# gtp.net
KiCad netlist of a schematic drawn in Altium Designer
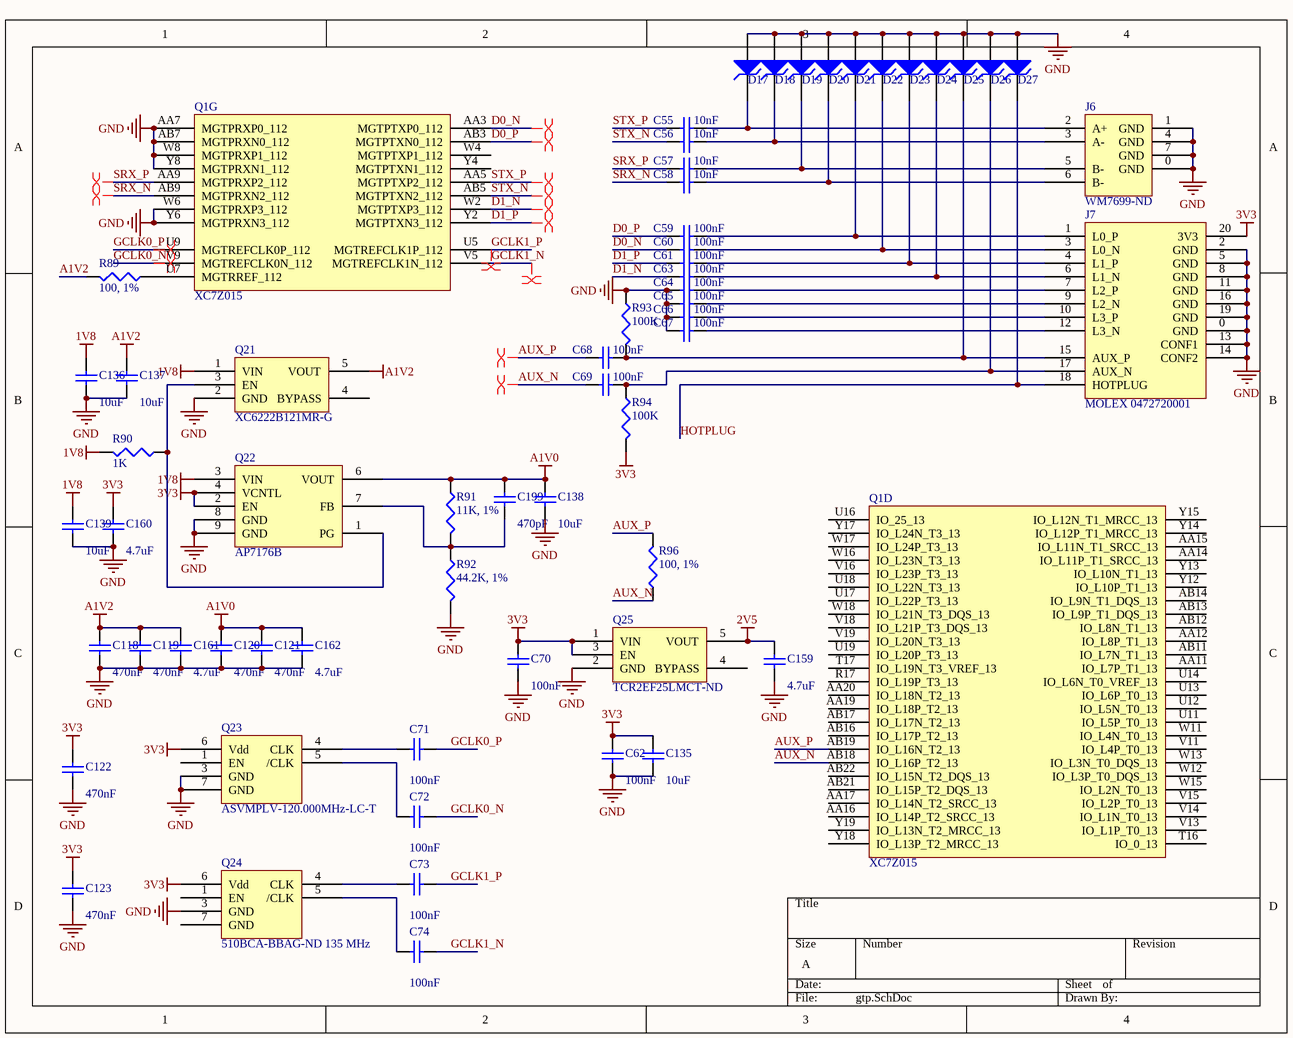
[diagram p0: gtp.SchDoc]

(export (version "E")
  (design (tool "Eeschema 10.0.6"))
  (components
    (comp (ref "C55")
      (value "10nF")
      (footprint "CAPC1005X06L")
      (description "Capacitor")
      (fields (field (name "Comment") "Cap") (field (name "PUBLISHER") "Altium Limited"))
      (libsource (lib "Miscellaneous Devices") (part "Cap"))
    )
    (comp (ref "C56")
      (value "10nF")
      (footprint "CAPC1005X06L")
      (description "Capacitor")
      (fields (field (name "Comment") "Cap") (field (name "PUBLISHER") "Altium Limited"))
      (libsource (lib "Miscellaneous Devices") (part "Cap"))
    )
    (comp (ref "C57")
      (value "10nF")
      (footprint "CAPC1005X06L")
      (description "Capacitor")
      (fields (field (name "Comment") "Cap") (field (name "PUBLISHER") "Altium Limited"))
      (libsource (lib "Miscellaneous Devices") (part "Cap"))
    )
    (comp (ref "C58")
      (value "10nF")
      (footprint "CAPC1005X06L")
      (description "Capacitor")
      (fields (field (name "Comment") "Cap") (field (name "PUBLISHER") "Altium Limited"))
      (libsource (lib "Miscellaneous Devices") (part "Cap"))
    )
    (comp (ref "C59")
      (value "100nF")
      (footprint "CAPC1005X06L")
      (description "Capacitor")
      (fields (field (name "Comment") "Cap") (field (name "PUBLISHER") "Altium Limited"))
      (libsource (lib "Miscellaneous Devices") (part "Cap"))
    )
    (comp (ref "C60")
      (value "100nF")
      (footprint "CAPC1005X06L")
      (description "Capacitor")
      (fields (field (name "Comment") "Cap") (field (name "PUBLISHER") "Altium Limited"))
      (libsource (lib "Miscellaneous Devices") (part "Cap"))
    )
    (comp (ref "C61")
      (value "100nF")
      (footprint "CAPC1005X06L")
      (description "Capacitor")
      (fields (field (name "Comment") "Cap") (field (name "PUBLISHER") "Altium Limited"))
      (libsource (lib "Miscellaneous Devices") (part "Cap"))
    )
    (comp (ref "C62")
      (value "100nF")
      (footprint "CAPC1005X06L")
      (description "Capacitor")
      (fields (field (name "Comment") "Cap") (field (name "PUBLISHER") "Altium Limited"))
      (libsource (lib "Miscellaneous Devices") (part "Cap"))
    )
    (comp (ref "C63")
      (value "100nF")
      (footprint "CAPC1005X06L")
      (description "Capacitor")
      (fields (field (name "Comment") "Cap") (field (name "PUBLISHER") "Altium Limited"))
      (libsource (lib "Miscellaneous Devices") (part "Cap"))
    )
    (comp (ref "C64")
      (value "100nF")
      (footprint "CAPC1005X06L")
      (description "Capacitor")
      (fields (field (name "Comment") "Cap") (field (name "PUBLISHER") "Altium Limited"))
      (libsource (lib "Miscellaneous Devices") (part "Cap"))
    )
    (comp (ref "C65")
      (value "100nF")
      (footprint "CAPC1005X06L")
      (description "Capacitor")
      (fields (field (name "Comment") "Cap") (field (name "PUBLISHER") "Altium Limited"))
      (libsource (lib "Miscellaneous Devices") (part "Cap"))
    )
    (comp (ref "C66")
      (value "100nF")
      (footprint "CAPC1005X06L")
      (description "Capacitor")
      (fields (field (name "Comment") "Cap") (field (name "PUBLISHER") "Altium Limited"))
      (libsource (lib "Miscellaneous Devices") (part "Cap"))
    )
    (comp (ref "C67")
      (value "100nF")
      (footprint "CAPC1005X06L")
      (description "Capacitor")
      (fields (field (name "Comment") "Cap") (field (name "PUBLISHER") "Altium Limited"))
      (libsource (lib "Miscellaneous Devices") (part "Cap"))
    )
    (comp (ref "C68")
      (value "100nF")
      (footprint "CAPC1005X06L")
      (description "Capacitor")
      (fields (field (name "Comment") "Cap") (field (name "PUBLISHER") "Altium Limited"))
      (libsource (lib "Miscellaneous Devices") (part "Cap"))
    )
    (comp (ref "C69")
      (value "100nF")
      (footprint "CAPC1005X06L")
      (description "Capacitor")
      (fields (field (name "Comment") "Cap") (field (name "PUBLISHER") "Altium Limited"))
      (libsource (lib "Miscellaneous Devices") (part "Cap"))
    )
    (comp (ref "C70")
      (value "100nF")
      (footprint "CAPC1005X06L")
      (description "Capacitor")
      (fields (field (name "Comment") "Cap") (field (name "PUBLISHER") "Altium Limited"))
      (libsource (lib "Miscellaneous Devices") (part "Cap"))
    )
    (comp (ref "C71")
      (value "100nF")
      (footprint "CAPC1005X06L")
      (description "Capacitor")
      (fields (field (name "Comment") "Cap") (field (name "PUBLISHER") "Altium Limited"))
      (libsource (lib "Miscellaneous Devices") (part "Cap"))
    )
    (comp (ref "C72")
      (value "100nF")
      (footprint "CAPC1005X06L")
      (description "Capacitor")
      (fields (field (name "Comment") "Cap") (field (name "PUBLISHER") "Altium Limited"))
      (libsource (lib "Miscellaneous Devices") (part "Cap"))
    )
    (comp (ref "C73")
      (value "100nF")
      (footprint "CAPC1005X06L")
      (description "Capacitor")
      (fields (field (name "Comment") "Cap") (field (name "PUBLISHER") "Altium Limited"))
      (libsource (lib "Miscellaneous Devices") (part "Cap"))
    )
    (comp (ref "C74")
      (value "100nF")
      (footprint "CAPC1005X06L")
      (description "Capacitor")
      (fields (field (name "Comment") "Cap") (field (name "PUBLISHER") "Altium Limited"))
      (libsource (lib "Miscellaneous Devices") (part "Cap"))
    )
    (comp (ref "C118")
      (value "470nF")
      (footprint "CAPC1005X06L")
      (description "Capacitor")
      (fields (field (name "Comment") "JMK105BJ474KV-F") (field (name "PUBLISHER") "Altium Limited"))
      (libsource (lib "Miscellaneous Devices") (part "Cap"))
    )
    (comp (ref "C119")
      (value "470nF")
      (footprint "CAPC1005X06L")
      (description "Capacitor")
      (fields (field (name "Comment") "JMK105BJ474KV-F") (field (name "PUBLISHER") "Altium Limited"))
      (libsource (lib "Miscellaneous Devices") (part "Cap"))
    )
    (comp (ref "C120")
      (value "470nF")
      (footprint "CAPC1005X06L")
      (description "Capacitor")
      (fields (field (name "Comment") "JMK105BJ474KV-F") (field (name "PUBLISHER") "Altium Limited"))
      (libsource (lib "Miscellaneous Devices") (part "Cap"))
    )
    (comp (ref "C121")
      (value "470nF")
      (footprint "CAPC1005X06L")
      (description "Capacitor")
      (fields (field (name "Comment") "JMK105BJ474KV-F") (field (name "PUBLISHER") "Altium Limited"))
      (libsource (lib "Miscellaneous Devices") (part "Cap"))
    )
    (comp (ref "C122")
      (value "470nF")
      (footprint "CAPC1005X06L")
      (description "Capacitor")
      (fields (field (name "Comment") "JMK105BJ474KV-F") (field (name "PUBLISHER") "Altium Limited"))
      (libsource (lib "Miscellaneous Devices") (part "Cap"))
    )
    (comp (ref "C123")
      (value "470nF")
      (footprint "CAPC1005X06L")
      (description "Capacitor")
      (fields (field (name "Comment") "JMK105BJ474KV-F") (field (name "PUBLISHER") "Altium Limited"))
      (libsource (lib "Miscellaneous Devices") (part "Cap"))
    )
    (comp (ref "C135")
      (value "10uF")
      (footprint "CAPC1608X90N")
      (description "Capacitor")
      (fields (field (name "Comment") "GRM188R60G106ME47") (field (name "PUBLISHER") "Altium Limited"))
      (libsource (lib "Miscellaneous Devices") (part "Cap"))
    )
    (comp (ref "C136")
      (value "10uF")
      (footprint "CAPC1608X90N")
      (description "Capacitor")
      (fields (field (name "Comment") "GRM188R60G106ME47") (field (name "PUBLISHER") "Altium Limited"))
      (libsource (lib "Miscellaneous Devices") (part "Cap"))
    )
    (comp (ref "C137")
      (value "10uF")
      (footprint "CAPC1608X90N")
      (description "Capacitor")
      (fields (field (name "Comment") "GRM188R60G106ME47") (field (name "PUBLISHER") "Altium Limited"))
      (libsource (lib "Miscellaneous Devices") (part "Cap"))
    )
    (comp (ref "C138")
      (value "10uF")
      (footprint "CAPC1608X90N")
      (description "Capacitor")
      (fields (field (name "Comment") "GRM188R60G106ME47") (field (name "PUBLISHER") "Altium Limited"))
      (libsource (lib "Miscellaneous Devices") (part "Cap"))
    )
    (comp (ref "C139")
      (value "10uF")
      (footprint "CAPC1608X90N")
      (description "Capacitor")
      (fields (field (name "Comment") "GRM188R60G106ME47") (field (name "PUBLISHER") "Altium Limited"))
      (libsource (lib "Miscellaneous Devices") (part "Cap"))
    )
    (comp (ref "C159")
      (value "4.7uF")
      (footprint "CAPC1608X90N")
      (description "Capacitor")
      (fields (field (name "Comment") "GRM188R60J475ME19D") (field (name "PUBLISHER") "Altium Limited"))
      (libsource (lib "Miscellaneous Devices") (part "Cap"))
    )
    (comp (ref "C160")
      (value "4.7uF")
      (footprint "CAPC1608X90N")
      (description "Capacitor")
      (fields (field (name "Comment") "GRM188R60J475ME19D") (field (name "PUBLISHER") "Altium Limited"))
      (libsource (lib "Miscellaneous Devices") (part "Cap"))
    )
    (comp (ref "C161")
      (value "4.7uF")
      (footprint "CAPC1608X90N")
      (description "Capacitor")
      (fields (field (name "Comment") "GRM188R60J475ME19D") (field (name "PUBLISHER") "Altium Limited"))
      (libsource (lib "Miscellaneous Devices") (part "Cap"))
    )
    (comp (ref "C162")
      (value "4.7uF")
      (footprint "CAPC1608X90N")
      (description "Capacitor")
      (fields (field (name "Comment") "GRM188R60J475ME19D") (field (name "PUBLISHER") "Altium Limited"))
      (libsource (lib "Miscellaneous Devices") (part "Cap"))
    )
    (comp (ref "C199")
      (value "470pF")
      (footprint "CAPC1608X90N")
      (description "Capacitor")
      (fields (field (name "Comment") "CL10C471JB8NCNC") (field (name "PUBLISHER") "Altium Limited"))
      (libsource (lib "Miscellaneous Devices") (part "Cap"))
    )
    (comp (ref "D17")
      (value "EZAEG2A")
      (footprint "CAPC1005X55N")
      (description "Zener Diode")
      (fields (field (name "PUBLISHER") "Altium Limited"))
      (libsource (lib "Miscellaneous Devices") (part "D Zener"))
    )
    (comp (ref "D18")
      (value "EZAEG2A")
      (footprint "CAPC1005X55N")
      (description "Zener Diode")
      (fields (field (name "PUBLISHER") "Altium Limited"))
      (libsource (lib "Miscellaneous Devices") (part "D Zener"))
    )
    (comp (ref "D19")
      (value "EZAEG2A")
      (footprint "CAPC1005X55N")
      (description "Zener Diode")
      (fields (field (name "PUBLISHER") "Altium Limited"))
      (libsource (lib "Miscellaneous Devices") (part "D Zener"))
    )
    (comp (ref "D20")
      (value "EZAEG2A")
      (footprint "CAPC1005X55N")
      (description "Zener Diode")
      (fields (field (name "PUBLISHER") "Altium Limited"))
      (libsource (lib "Miscellaneous Devices") (part "D Zener"))
    )
    (comp (ref "D21")
      (value "EZAEG2A")
      (footprint "CAPC1005X55N")
      (description "Zener Diode")
      (fields (field (name "PUBLISHER") "Altium Limited"))
      (libsource (lib "Miscellaneous Devices") (part "D Zener"))
    )
    (comp (ref "D22")
      (value "EZAEG2A")
      (footprint "CAPC1005X55N")
      (description "Zener Diode")
      (fields (field (name "PUBLISHER") "Altium Limited"))
      (libsource (lib "Miscellaneous Devices") (part "D Zener"))
    )
    (comp (ref "D23")
      (value "EZAEG2A")
      (footprint "CAPC1005X55N")
      (description "Zener Diode")
      (fields (field (name "PUBLISHER") "Altium Limited"))
      (libsource (lib "Miscellaneous Devices") (part "D Zener"))
    )
    (comp (ref "D24")
      (value "EZAEG2A")
      (footprint "CAPC1005X55N")
      (description "Zener Diode")
      (fields (field (name "PUBLISHER") "Altium Limited"))
      (libsource (lib "Miscellaneous Devices") (part "D Zener"))
    )
    (comp (ref "D25")
      (value "EZAEG2A")
      (footprint "CAPC1005X55N")
      (description "Zener Diode")
      (fields (field (name "PUBLISHER") "Altium Limited"))
      (libsource (lib "Miscellaneous Devices") (part "D Zener"))
    )
    (comp (ref "D26")
      (value "EZAEG2A")
      (footprint "CAPC1005X55N")
      (description "Zener Diode")
      (fields (field (name "PUBLISHER") "Altium Limited"))
      (libsource (lib "Miscellaneous Devices") (part "D Zener"))
    )
    (comp (ref "D27")
      (value "EZAEG2A")
      (footprint "CAPC1005X55N")
      (description "Zener Diode")
      (fields (field (name "PUBLISHER") "Altium Limited"))
      (libsource (lib "Miscellaneous Devices") (part "D Zener"))
    )
    (comp (ref "J6")
      (value "WM7699-ND")
      (footprint "WM7699-ND")
      (libsource (lib "schlib") (part "WM7699-ND"))
    )
    (comp (ref "J7")
      (value "MOLEX 0472720001")
      (footprint "MOLEX0472720001")
      (libsource (lib "schlib") (part "DP"))
    )
    (comp (ref "Q1") (value "XC7Z015") (footprint "BGA484x22") (libsource (lib "schlib") (part "XC7Z015")))
    (comp (ref "Q21") (value "XC6222B121MR-G") (footprint "SOT23-5") (libsource (lib "schlib") (part "LDO")))
    (comp (ref "Q22")
      (value "AP7176B")
      (footprint "SOIC127P600X135_HS-9N")
      (libsource (lib "schlib") (part "AP7176B"))
    )
    (comp (ref "Q23")
      (value "ASVMPLV-120.000MHz-LC-T")
      (footprint "ASVMP")
      (libsource (lib "schlib") (part "ASVMP"))
    )
    (comp (ref "Q24")
      (value "510BCA-BBAG-ND 135 MHz")
      (footprint "Si510")
      (libsource (lib "schlib") (part "ASVMP"))
    )
    (comp (ref "Q25") (value "TCR2EF25LMCT-ND") (footprint "SOT23-5") (libsource (lib "schlib") (part "LDO")))
    (comp (ref "R89")
      (value "100, 1%")
      (footprint "J1-0603")
      (description "Resistor")
      (fields (field (name "Comment") "RC1608F101CS") (field (name "PUBLISHER") "Altium Limited"))
      (libsource (lib "Miscellaneous Devices") (part "Res3"))
    )
    (comp (ref "R90")
      (value "1K")
      (footprint "J1-0603")
      (description "Resistor")
      (fields (field (name "Comment") "RC1608J102CS") (field (name "PUBLISHER") "Altium Limited"))
      (libsource (lib "Miscellaneous Devices") (part "Res3"))
    )
    (comp (ref "R91")
      (value "11K, 1%")
      (footprint "J1-0603")
      (description "Resistor")
      (fields (field (name "Comment") "RC1608F113CS") (field (name "PUBLISHER") "Altium Limited"))
      (libsource (lib "Miscellaneous Devices") (part "Res3"))
    )
    (comp (ref "R92")
      (value "44.2K, 1%")
      (footprint "J1-0603")
      (description "Resistor")
      (fields (field (name "Comment") "RC1608F4422CS") (field (name "PUBLISHER") "Altium Limited"))
      (libsource (lib "Miscellaneous Devices") (part "Res3"))
    )
    (comp (ref "R93")
      (value "100K")
      (footprint "J1-0603")
      (description "Resistor")
      (fields (field (name "Comment") "RC1608F104CS") (field (name "PUBLISHER") "Altium Limited"))
      (libsource (lib "Miscellaneous Devices") (part "Res3"))
    )
    (comp (ref "R94")
      (value "100K")
      (footprint "J1-0603")
      (description "Resistor")
      (fields (field (name "Comment") "RC1608F104CS") (field (name "PUBLISHER") "Altium Limited"))
      (libsource (lib "Miscellaneous Devices") (part "Res3"))
    )
    (comp (ref "R96")
      (value "100, 1%")
      (footprint "J1-0603")
      (description "Resistor")
      (fields (field (name "Comment") "RC1608F101CS") (field (name "PUBLISHER") "Altium Limited"))
      (libsource (lib "Miscellaneous Devices") (part "Res3"))
    )
  )
  (nets
    (net (code "1") (name "/AUX_N") (class "Default")
      (node (ref "C69") (pin "2") (pinfunction "2_2") (pintype "passive"))
      (node (ref "Q1") (pin "AB18") (pinfunction "IO_L16P_T2_13_AB18") (pintype "passive"))
      (node (ref "R96") (pin "1") (pinfunction "1_1") (pintype "passive"))
    )
    (net (code "2") (name "/AUX_P") (class "Default")
      (node (ref "C68") (pin "2") (pinfunction "2_2") (pintype "passive"))
      (node (ref "Q1") (pin "AB19") (pinfunction "IO_L16N_T2_13_AB19") (pintype "passive"))
      (node (ref "R96") (pin "2") (pinfunction "2_2") (pintype "passive"))
    )
    (net (code "3") (name "/D0_N") (class "Default")
      (node (ref "C60") (pin "2") (pinfunction "2_2") (pintype "passive"))
      (node (ref "Q1") (pin "AA3") (pinfunction "MGTPTXP0_112_AA3") (pintype "passive"))
    )
    (net (code "4") (name "/D0_P") (class "Default")
      (node (ref "C59") (pin "2") (pinfunction "2_2") (pintype "passive"))
      (node (ref "Q1") (pin "AB3") (pinfunction "MGTPTXN0_112_AB3") (pintype "passive"))
    )
    (net (code "5") (name "/D1_N") (class "Default")
      (node (ref "C63") (pin "2") (pinfunction "2_2") (pintype "passive"))
      (node (ref "Q1") (pin "W2") (pinfunction "MGTPTXP3_112_W2") (pintype "passive"))
    )
    (net (code "6") (name "/D1_P") (class "Default")
      (node (ref "C61") (pin "2") (pinfunction "2_2") (pintype "passive"))
      (node (ref "Q1") (pin "Y2") (pinfunction "MGTPTXN3_112_Y2") (pintype "passive"))
    )
    (net (code "7") (name "/GCLK0_N") (class "Default")
      (node (ref "C72") (pin "1") (pinfunction "1_1") (pintype "passive"))
      (node (ref "Q1") (pin "V9") (pinfunction "MGTREFCLK0N_112_V9") (pintype "passive"))
    )
    (net (code "8") (name "/GCLK0_P") (class "Default")
      (node (ref "C71") (pin "1") (pinfunction "1_1") (pintype "passive"))
      (node (ref "Q1") (pin "U9") (pinfunction "MGTREFCLK0P_112_U9") (pintype "passive"))
    )
    (net (code "9") (name "/GCLK1_N") (class "Default")
      (node (ref "C74") (pin "1") (pinfunction "1_1") (pintype "passive"))
      (node (ref "Q1") (pin "V5") (pinfunction "MGTREFCLK1N_112_V5") (pintype "passive"))
    )
    (net (code "10") (name "/GCLK1_P") (class "Default")
      (node (ref "C73") (pin "1") (pinfunction "1_1") (pintype "passive"))
      (node (ref "Q1") (pin "U5") (pinfunction "MGTREFCLK1P_112_U5") (pintype "passive"))
    )
    (net (code "11") (name "/HOTPLUG") (class "Default")
      (node (ref "D27") (pin "2") (pinfunction "K_2") (pintype "passive"))
      (node (ref "J7") (pin "18") (pinfunction "HOTPLUG_18") (pintype "passive"))
    )
    (net (code "12") (name "/SRX_N") (class "Default")
      (node (ref "C58") (pin "2") (pinfunction "2_2") (pintype "passive"))
      (node (ref "Q1") (pin "AB9") (pinfunction "MGTPRXN2_112_AB9") (pintype "passive"))
    )
    (net (code "13") (name "/SRX_P") (class "Default")
      (node (ref "C57") (pin "2") (pinfunction "2_2") (pintype "passive"))
      (node (ref "Q1") (pin "AA9") (pinfunction "MGTPRXP2_112_AA9") (pintype "passive"))
    )
    (net (code "14") (name "/STX_N") (class "Default")
      (node (ref "C56") (pin "2") (pinfunction "2_2") (pintype "passive"))
      (node (ref "Q1") (pin "AB5") (pinfunction "MGTPTXN2_112_AB5") (pintype "passive"))
    )
    (net (code "15") (name "/STX_P") (class "Default")
      (node (ref "C55") (pin "2") (pinfunction "2_2") (pintype "passive"))
      (node (ref "Q1") (pin "AA5") (pinfunction "MGTPTXP2_112_AA5") (pintype "passive"))
    )
    (net (code "16") (name "1V8") (class "Default")
      (node (ref "C136") (pin "2") (pinfunction "2_2") (pintype "passive"))
      (node (ref "C139") (pin "2") (pinfunction "2_2") (pintype "passive"))
      (node (ref "Q21") (pin "1") (pinfunction "VIN_1") (pintype "passive"))
      (node (ref "Q22") (pin "3") (pinfunction "VIN_3") (pintype "passive"))
      (node (ref "R90") (pin "2") (pinfunction "2_2") (pintype "passive"))
    )
    (net (code "17") (name "2V5") (class "Default")
      (node (ref "C159") (pin "1") (pinfunction "1_1") (pintype "passive"))
      (node (ref "Q25") (pin "5") (pinfunction "VOUT_5") (pintype "passive"))
    )
    (net (code "18") (name "3V3") (class "Default")
      (node (ref "C122") (pin "2") (pinfunction "2_2") (pintype "passive"))
      (node (ref "C123") (pin "2") (pinfunction "2_2") (pintype "passive"))
      (node (ref "C135") (pin "2") (pinfunction "2_2") (pintype "passive"))
      (node (ref "C160") (pin "1") (pinfunction "1_1") (pintype "passive"))
      (node (ref "C62") (pin "2") (pinfunction "2_2") (pintype "passive"))
      (node (ref "C70") (pin "2") (pinfunction "2_2") (pintype "passive"))
      (node (ref "J7") (pin "20") (pinfunction "3V3_20") (pintype "passive"))
      (node (ref "Q22") (pin "2") (pinfunction "EN_2") (pintype "passive"))
      (node (ref "Q22") (pin "4") (pinfunction "VCNTL_4") (pintype "passive"))
      (node (ref "Q23") (pin "6") (pinfunction "Vdd_6") (pintype "passive"))
      (node (ref "Q24") (pin "6") (pinfunction "Vdd_6") (pintype "passive"))
      (node (ref "Q25") (pin "1") (pinfunction "VIN_1") (pintype "passive"))
      (node (ref "Q25") (pin "3") (pinfunction "EN_3") (pintype "passive"))
      (node (ref "R94") (pin "2") (pinfunction "2_2") (pintype "passive"))
    )
    (net (code "19") (name "A1V0") (class "Default")
      (node (ref "C120") (pin "2") (pinfunction "2_2") (pintype "passive"))
      (node (ref "C121") (pin "2") (pinfunction "2_2") (pintype "passive"))
      (node (ref "C138") (pin "2") (pinfunction "2_2") (pintype "passive"))
      (node (ref "C162") (pin "1") (pinfunction "1_1") (pintype "passive"))
      (node (ref "C199") (pin "1") (pinfunction "1_1") (pintype "passive"))
      (node (ref "Q22") (pin "6") (pinfunction "VOUT_6") (pintype "passive"))
      (node (ref "R91") (pin "1") (pinfunction "1_1") (pintype "passive"))
    )
    (net (code "20") (name "A1V2") (class "Default")
      (node (ref "C118") (pin "2") (pinfunction "2_2") (pintype "passive"))
      (node (ref "C119") (pin "2") (pinfunction "2_2") (pintype "passive"))
      (node (ref "C137") (pin "2") (pinfunction "2_2") (pintype "passive"))
      (node (ref "C161") (pin "1") (pinfunction "1_1") (pintype "passive"))
      (node (ref "Q21") (pin "5") (pinfunction "VOUT_5") (pintype "passive"))
      (node (ref "R89") (pin "2") (pinfunction "2_2") (pintype "passive"))
    )
    (net (code "21") (name "GND") (class "Default")
      (node (ref "C118") (pin "1") (pinfunction "1_1") (pintype "passive"))
      (node (ref "C119") (pin "1") (pinfunction "1_1") (pintype "passive"))
      (node (ref "C120") (pin "1") (pinfunction "1_1") (pintype "passive"))
      (node (ref "C121") (pin "1") (pinfunction "1_1") (pintype "passive"))
      (node (ref "C122") (pin "1") (pinfunction "1_1") (pintype "passive"))
      (node (ref "C123") (pin "1") (pinfunction "1_1") (pintype "passive"))
      (node (ref "C135") (pin "1") (pinfunction "1_1") (pintype "passive"))
      (node (ref "C136") (pin "1") (pinfunction "1_1") (pintype "passive"))
      (node (ref "C137") (pin "1") (pinfunction "1_1") (pintype "passive"))
      (node (ref "C138") (pin "1") (pinfunction "1_1") (pintype "passive"))
      (node (ref "C139") (pin "1") (pinfunction "1_1") (pintype "passive"))
      (node (ref "C159") (pin "2") (pinfunction "2_2") (pintype "passive"))
      (node (ref "C160") (pin "2") (pinfunction "2_2") (pintype "passive"))
      (node (ref "C161") (pin "2") (pinfunction "2_2") (pintype "passive"))
      (node (ref "C162") (pin "2") (pinfunction "2_2") (pintype "passive"))
      (node (ref "C62") (pin "1") (pinfunction "1_1") (pintype "passive"))
      (node (ref "C64") (pin "2") (pinfunction "2_2") (pintype "passive"))
      (node (ref "C65") (pin "2") (pinfunction "2_2") (pintype "passive"))
      (node (ref "C66") (pin "2") (pinfunction "2_2") (pintype "passive"))
      (node (ref "C67") (pin "2") (pinfunction "2_2") (pintype "passive"))
      (node (ref "C70") (pin "1") (pinfunction "1_1") (pintype "passive"))
      (node (ref "D17") (pin "1") (pinfunction "A_1") (pintype "passive"))
      (node (ref "D18") (pin "1") (pinfunction "A_1") (pintype "passive"))
      (node (ref "D19") (pin "1") (pinfunction "A_1") (pintype "passive"))
      (node (ref "D20") (pin "1") (pinfunction "A_1") (pintype "passive"))
      (node (ref "D21") (pin "1") (pinfunction "A_1") (pintype "passive"))
      (node (ref "D22") (pin "1") (pinfunction "A_1") (pintype "passive"))
      (node (ref "D23") (pin "1") (pinfunction "A_1") (pintype "passive"))
      (node (ref "D24") (pin "1") (pinfunction "A_1") (pintype "passive"))
      (node (ref "D25") (pin "1") (pinfunction "A_1") (pintype "passive"))
      (node (ref "D26") (pin "1") (pinfunction "A_1") (pintype "passive"))
      (node (ref "D27") (pin "1") (pinfunction "A_1") (pintype "passive"))
      (node (ref "J6") (pin "0") (pinfunction "GND_0") (pintype "passive"))
      (node (ref "J6") (pin "1") (pinfunction "GND_1") (pintype "passive"))
      (node (ref "J6") (pin "4") (pinfunction "GND_4") (pintype "passive"))
      (node (ref "J6") (pin "7") (pinfunction "GND_7") (pintype "passive"))
      (node (ref "J7") (pin "0") (pinfunction "GND_0") (pintype "passive"))
      (node (ref "J7") (pin "11") (pinfunction "GND_11") (pintype "passive"))
      (node (ref "J7") (pin "13") (pinfunction "CONF1_13") (pintype "passive"))
      (node (ref "J7") (pin "14") (pinfunction "CONF2_14") (pintype "passive"))
      (node (ref "J7") (pin "16") (pinfunction "GND_16") (pintype "passive"))
      (node (ref "J7") (pin "19") (pinfunction "GND_19") (pintype "passive"))
      (node (ref "J7") (pin "2") (pinfunction "GND_2") (pintype "passive"))
      (node (ref "J7") (pin "5") (pinfunction "GND_5") (pintype "passive"))
      (node (ref "J7") (pin "8") (pinfunction "GND_8") (pintype "passive"))
      (node (ref "Q1") (pin "AA7") (pinfunction "MGTPRXP0_112_AA7") (pintype "passive"))
      (node (ref "Q1") (pin "AB7") (pinfunction "MGTPRXN0_112_AB7") (pintype "passive"))
      (node (ref "Q1") (pin "W6") (pinfunction "MGTPRXP3_112_W6") (pintype "passive"))
      (node (ref "Q1") (pin "W8") (pinfunction "MGTPRXP1_112_W8") (pintype "passive"))
      (node (ref "Q1") (pin "Y6") (pinfunction "MGTPRXN3_112_Y6") (pintype "passive"))
      (node (ref "Q1") (pin "Y8") (pinfunction "MGTPRXN1_112_Y8") (pintype "passive"))
      (node (ref "Q21") (pin "2") (pinfunction "GND_2") (pintype "passive"))
      (node (ref "Q22") (pin "8") (pinfunction "GND_8") (pintype "passive"))
      (node (ref "Q22") (pin "9") (pinfunction "GND_9") (pintype "passive"))
      (node (ref "Q23") (pin "3") (pinfunction "GND_3") (pintype "passive"))
      (node (ref "Q23") (pin "7") (pinfunction "GND_7") (pintype "passive"))
      (node (ref "Q24") (pin "3") (pinfunction "GND_3") (pintype "passive"))
      (node (ref "Q25") (pin "2") (pinfunction "GND_2") (pintype "passive"))
      (node (ref "R92") (pin "2") (pinfunction "2_2") (pintype "passive"))
      (node (ref "R93") (pin "1") (pinfunction "1_1") (pintype "passive"))
    )
    (net (code "22") (name "Net-(D17-K)") (class "Default")
      (node (ref "C55") (pin "1") (pinfunction "1_1") (pintype "passive"))
      (node (ref "D17") (pin "2") (pinfunction "K_2") (pintype "passive"))
      (node (ref "J6") (pin "2") (pinfunction "A+_2") (pintype "passive"))
    )
    (net (code "23") (name "Net-(D18-K)") (class "Default")
      (node (ref "C56") (pin "1") (pinfunction "1_1") (pintype "passive"))
      (node (ref "D18") (pin "2") (pinfunction "K_2") (pintype "passive"))
      (node (ref "J6") (pin "3") (pinfunction "A-_3") (pintype "passive"))
    )
    (net (code "24") (name "Net-(D19-K)") (class "Default")
      (node (ref "C57") (pin "1") (pinfunction "1_1") (pintype "passive"))
      (node (ref "D19") (pin "2") (pinfunction "K_2") (pintype "passive"))
      (node (ref "J6") (pin "5") (pinfunction "B-_5") (pintype "passive"))
    )
    (net (code "25") (name "Net-(D20-K)") (class "Default")
      (node (ref "C58") (pin "1") (pinfunction "1_1") (pintype "passive"))
      (node (ref "D20") (pin "2") (pinfunction "K_2") (pintype "passive"))
      (node (ref "J6") (pin "6") (pinfunction "B-_6") (pintype "passive"))
    )
    (net (code "26") (name "Net-(D21-K)") (class "Default")
      (node (ref "C59") (pin "1") (pinfunction "1_1") (pintype "passive"))
      (node (ref "D21") (pin "2") (pinfunction "K_2") (pintype "passive"))
      (node (ref "J7") (pin "1") (pinfunction "L0_P_1") (pintype "passive"))
    )
    (net (code "27") (name "Net-(D22-K)") (class "Default")
      (node (ref "C60") (pin "1") (pinfunction "1_1") (pintype "passive"))
      (node (ref "D22") (pin "2") (pinfunction "K_2") (pintype "passive"))
      (node (ref "J7") (pin "3") (pinfunction "L0_N_3") (pintype "passive"))
    )
    (net (code "28") (name "Net-(D23-K)") (class "Default")
      (node (ref "C61") (pin "1") (pinfunction "1_1") (pintype "passive"))
      (node (ref "D23") (pin "2") (pinfunction "K_2") (pintype "passive"))
      (node (ref "J7") (pin "4") (pinfunction "L1_P_4") (pintype "passive"))
    )
    (net (code "29") (name "Net-(D24-K)") (class "Default")
      (node (ref "C63") (pin "1") (pinfunction "1_1") (pintype "passive"))
      (node (ref "D24") (pin "2") (pinfunction "K_2") (pintype "passive"))
      (node (ref "J7") (pin "6") (pinfunction "L1_N_6") (pintype "passive"))
    )
    (net (code "30") (name "Net-(D25-K)") (class "Default")
      (node (ref "C68") (pin "1") (pinfunction "1_1") (pintype "passive"))
      (node (ref "D25") (pin "2") (pinfunction "K_2") (pintype "passive"))
      (node (ref "J7") (pin "15") (pinfunction "AUX_P_15") (pintype "passive"))
      (node (ref "R93") (pin "2") (pinfunction "2_2") (pintype "passive"))
    )
    (net (code "31") (name "Net-(D26-K)") (class "Default")
      (node (ref "C69") (pin "1") (pinfunction "1_1") (pintype "passive"))
      (node (ref "D26") (pin "2") (pinfunction "K_2") (pintype "passive"))
      (node (ref "J7") (pin "17") (pinfunction "AUX_N_17") (pintype "passive"))
      (node (ref "R94") (pin "1") (pinfunction "1_1") (pintype "passive"))
    )
    (net (code "32") (name "Net-(J7-L2_N)") (class "Default")
      (node (ref "C65") (pin "1") (pinfunction "1_1") (pintype "passive"))
      (node (ref "J7") (pin "9") (pinfunction "L2_N_9") (pintype "passive"))
    )
    (net (code "33") (name "Net-(J7-L2_P)") (class "Default")
      (node (ref "C64") (pin "1") (pinfunction "1_1") (pintype "passive"))
      (node (ref "J7") (pin "7") (pinfunction "L2_P_7") (pintype "passive"))
    )
    (net (code "34") (name "Net-(J7-L3_N)") (class "Default")
      (node (ref "C67") (pin "1") (pinfunction "1_1") (pintype "passive"))
      (node (ref "J7") (pin "12") (pinfunction "L3_N_12") (pintype "passive"))
    )
    (net (code "35") (name "Net-(J7-L3_P)") (class "Default")
      (node (ref "C66") (pin "1") (pinfunction "1_1") (pintype "passive"))
      (node (ref "J7") (pin "10") (pinfunction "L3_P_10") (pintype "passive"))
    )
    (net (code "36") (name "Net-(Q1G-MGTRREF_112)") (class "Default")
      (node (ref "Q1") (pin "U7") (pinfunction "MGTRREF_112_U7") (pintype "passive"))
      (node (ref "R89") (pin "1") (pinfunction "1_1") (pintype "passive"))
    )
    (net (code "37") (name "Net-(Q21-EN)") (class "Default")
      (node (ref "Q21") (pin "3") (pinfunction "EN_3") (pintype "passive"))
      (node (ref "Q22") (pin "1") (pinfunction "PG_1") (pintype "passive"))
      (node (ref "R90") (pin "1") (pinfunction "1_1") (pintype "passive"))
    )
    (net (code "38") (name "Net-(Q22-FB)") (class "Default")
      (node (ref "C199") (pin "2") (pinfunction "2_2") (pintype "passive"))
      (node (ref "Q22") (pin "7") (pinfunction "FB_7") (pintype "passive"))
      (node (ref "R91") (pin "2") (pinfunction "2_2") (pintype "passive"))
      (node (ref "R92") (pin "1") (pinfunction "1_1") (pintype "passive"))
    )
    (net (code "39") (name "Net-(Q23-CLK)") (class "Default")
      (node (ref "C71") (pin "2") (pinfunction "2_2") (pintype "passive"))
      (node (ref "Q23") (pin "4") (pinfunction "CLK_4") (pintype "passive"))
    )
    (net (code "40") (name "Net-(Q23-{slash}CLK)") (class "Default")
      (node (ref "C72") (pin "2") (pinfunction "2_2") (pintype "passive"))
      (node (ref "Q23") (pin "5") (pinfunction "/CLK_5") (pintype "passive"))
    )
    (net (code "41") (name "Net-(Q24-CLK)") (class "Default")
      (node (ref "C73") (pin "2") (pinfunction "2_2") (pintype "passive"))
      (node (ref "Q24") (pin "4") (pinfunction "CLK_4") (pintype "passive"))
    )
    (net (code "42") (name "Net-(Q24-{slash}CLK)") (class "Default")
      (node (ref "C74") (pin "2") (pinfunction "2_2") (pintype "passive"))
      (node (ref "Q24") (pin "5") (pinfunction "/CLK_5") (pintype "passive"))
    )
    (net (code "43") (name "unconnected-(Q1D-IO_0_13-PadT16)") (class "Default")
      (node (ref "Q1") (pin "T16") (pinfunction "IO_0_13_T16") (pintype "passive"))
    )
    (net (code "44") (name "unconnected-(Q1D-IO_25_13-PadU16)") (class "Default")
      (node (ref "Q1") (pin "U16") (pinfunction "IO_25_13_U16") (pintype "passive"))
    )
    (net (code "45") (name "unconnected-(Q1D-IO_L1N_T0_13-PadV14)") (class "Default")
      (node (ref "Q1") (pin "V14") (pinfunction "IO_L1N_T0_13_V14") (pintype "passive"))
    )
    (net (code "46") (name "unconnected-(Q1D-IO_L1P_T0_13-PadV13)") (class "Default")
      (node (ref "Q1") (pin "V13") (pinfunction "IO_L1P_T0_13_V13") (pintype "passive"))
    )
    (net (code "47") (name "unconnected-(Q1D-IO_L2N_T0_13-PadW15)") (class "Default")
      (node (ref "Q1") (pin "W15") (pinfunction "IO_L2N_T0_13_W15") (pintype "passive"))
    )
    (net (code "48") (name "unconnected-(Q1D-IO_L2P_T0_13-PadV15)") (class "Default")
      (node (ref "Q1") (pin "V15") (pinfunction "IO_L2P_T0_13_V15") (pintype "passive"))
    )
    (net (code "49") (name "unconnected-(Q1D-IO_L3N_T0_DQS_13-PadW13)") (class "Default")
      (node (ref "Q1") (pin "W13") (pinfunction "IO_L3N_T0_DQS_13_W13") (pintype "passive"))
    )
    (net (code "50") (name "unconnected-(Q1D-IO_L3P_T0_DQS_13-PadW12)") (class "Default")
      (node (ref "Q1") (pin "W12") (pinfunction "IO_L3P_T0_DQS_13_W12") (pintype "passive"))
    )
    (net (code "51") (name "unconnected-(Q1D-IO_L4N_T0_13-PadW11)") (class "Default")
      (node (ref "Q1") (pin "W11") (pinfunction "IO_L4N_T0_13_W11") (pintype "passive"))
    )
    (net (code "52") (name "unconnected-(Q1D-IO_L4P_T0_13-PadV11)") (class "Default")
      (node (ref "Q1") (pin "V11") (pinfunction "IO_L4P_T0_13_V11") (pintype "passive"))
    )
    (net (code "53") (name "unconnected-(Q1D-IO_L5N_T0_13-PadU12)") (class "Default")
      (node (ref "Q1") (pin "U12") (pinfunction "IO_L5N_T0_13_U12") (pintype "passive"))
    )
    (net (code "54") (name "unconnected-(Q1D-IO_L5P_T0_13-PadU11)") (class "Default")
      (node (ref "Q1") (pin "U11") (pinfunction "IO_L5P_T0_13_U11") (pintype "passive"))
    )
    (net (code "55") (name "unconnected-(Q1D-IO_L6N_T0_VREF_13-PadU14)") (class "Default")
      (node (ref "Q1") (pin "U14") (pinfunction "IO_L6N_T0_VREF_13_U14") (pintype "passive"))
    )
    (net (code "56") (name "unconnected-(Q1D-IO_L6P_T0_13-PadU13)") (class "Default")
      (node (ref "Q1") (pin "U13") (pinfunction "IO_L6P_T0_13_U13") (pintype "passive"))
    )
    (net (code "57") (name "unconnected-(Q1D-IO_L7N_T1_13-PadAB11)") (class "Default")
      (node (ref "Q1") (pin "AB11") (pinfunction "IO_L7N_T1_13_AB11") (pintype "passive"))
    )
    (net (code "58") (name "unconnected-(Q1D-IO_L7P_T1_13-PadAA11)") (class "Default")
      (node (ref "Q1") (pin "AA11") (pinfunction "IO_L7P_T1_13_AA11") (pintype "passive"))
    )
    (net (code "59") (name "unconnected-(Q1D-IO_L8N_T1_13-PadAB12)") (class "Default")
      (node (ref "Q1") (pin "AB12") (pinfunction "IO_L8N_T1_13_AB12") (pintype "passive"))
    )
    (net (code "60") (name "unconnected-(Q1D-IO_L8P_T1_13-PadAA12)") (class "Default")
      (node (ref "Q1") (pin "AA12") (pinfunction "IO_L8P_T1_13_AA12") (pintype "passive"))
    )
    (net (code "61") (name "unconnected-(Q1D-IO_L9N_T1_DQS_13-PadAB14)") (class "Default")
      (node (ref "Q1") (pin "AB14") (pinfunction "IO_L9N_T1_DQS_13_AB14") (pintype "passive"))
    )
    (net (code "62") (name "unconnected-(Q1D-IO_L9P_T1_DQS_13-PadAB13)") (class "Default")
      (node (ref "Q1") (pin "AB13") (pinfunction "IO_L9P_T1_DQS_13_AB13") (pintype "passive"))
    )
    (net (code "63") (name "unconnected-(Q1D-IO_L10N_T1_13-PadY13)") (class "Default")
      (node (ref "Q1") (pin "Y13") (pinfunction "IO_L10N_T1_13_Y13") (pintype "passive"))
    )
    (net (code "64") (name "unconnected-(Q1D-IO_L10P_T1_13-PadY12)") (class "Default")
      (node (ref "Q1") (pin "Y12") (pinfunction "IO_L10P_T1_13_Y12") (pintype "passive"))
    )
    (net (code "65") (name "unconnected-(Q1D-IO_L11N_T1_SRCC_13-PadAA15)") (class "Default")
      (node (ref "Q1") (pin "AA15") (pinfunction "IO_L11N_T1_SRCC_13_AA15") (pintype "passive"))
    )
    (net (code "66") (name "unconnected-(Q1D-IO_L11P_T1_SRCC_13-PadAA14)") (class "Default")
      (node (ref "Q1") (pin "AA14") (pinfunction "IO_L11P_T1_SRCC_13_AA14") (pintype "passive"))
    )
    (net (code "67") (name "unconnected-(Q1D-IO_L12N_T1_MRCC_13-PadY15)") (class "Default")
      (node (ref "Q1") (pin "Y15") (pinfunction "IO_L12N_T1_MRCC_13_Y15") (pintype "passive"))
    )
    (net (code "68") (name "unconnected-(Q1D-IO_L12P_T1_MRCC_13-PadY14)") (class "Default")
      (node (ref "Q1") (pin "Y14") (pinfunction "IO_L12P_T1_MRCC_13_Y14") (pintype "passive"))
    )
    (net (code "69") (name "unconnected-(Q1D-IO_L13N_T2_MRCC_13-PadY19)") (class "Default")
      (node (ref "Q1") (pin "Y19") (pinfunction "IO_L13N_T2_MRCC_13_Y19") (pintype "passive"))
    )
    (net (code "70") (name "unconnected-(Q1D-IO_L13P_T2_MRCC_13-PadY18)") (class "Default")
      (node (ref "Q1") (pin "Y18") (pinfunction "IO_L13P_T2_MRCC_13_Y18") (pintype "passive"))
    )
    (net (code "71") (name "unconnected-(Q1D-IO_L14N_T2_SRCC_13-PadAA17)") (class "Default")
      (node (ref "Q1") (pin "AA17") (pinfunction "IO_L14N_T2_SRCC_13_AA17") (pintype "passive"))
    )
    (net (code "72") (name "unconnected-(Q1D-IO_L14P_T2_SRCC_13-PadAA16)") (class "Default")
      (node (ref "Q1") (pin "AA16") (pinfunction "IO_L14P_T2_SRCC_13_AA16") (pintype "passive"))
    )
    (net (code "73") (name "unconnected-(Q1D-IO_L15N_T2_DQS_13-PadAB22)") (class "Default")
      (node (ref "Q1") (pin "AB22") (pinfunction "IO_L15N_T2_DQS_13_AB22") (pintype "passive"))
    )
    (net (code "74") (name "unconnected-(Q1D-IO_L15P_T2_DQS_13-PadAB21)") (class "Default")
      (node (ref "Q1") (pin "AB21") (pinfunction "IO_L15P_T2_DQS_13_AB21") (pintype "passive"))
    )
    (net (code "75") (name "unconnected-(Q1D-IO_L17N_T2_13-PadAB17)") (class "Default")
      (node (ref "Q1") (pin "AB17") (pinfunction "IO_L17N_T2_13_AB17") (pintype "passive"))
    )
    (net (code "76") (name "unconnected-(Q1D-IO_L17P_T2_13-PadAB16)") (class "Default")
      (node (ref "Q1") (pin "AB16") (pinfunction "IO_L17P_T2_13_AB16") (pintype "passive"))
    )
    (net (code "77") (name "unconnected-(Q1D-IO_L18N_T2_13-PadAA20)") (class "Default")
      (node (ref "Q1") (pin "AA20") (pinfunction "IO_L18N_T2_13_AA20") (pintype "passive"))
    )
    (net (code "78") (name "unconnected-(Q1D-IO_L18P_T2_13-PadAA19)") (class "Default")
      (node (ref "Q1") (pin "AA19") (pinfunction "IO_L18P_T2_13_AA19") (pintype "passive"))
    )
    (net (code "79") (name "unconnected-(Q1D-IO_L19N_T3_VREF_13-PadT17)") (class "Default")
      (node (ref "Q1") (pin "T17") (pinfunction "IO_L19N_T3_VREF_13_T17") (pintype "passive"))
    )
    (net (code "80") (name "unconnected-(Q1D-IO_L19P_T3_13-PadR17)") (class "Default")
      (node (ref "Q1") (pin "R17") (pinfunction "IO_L19P_T3_13_R17") (pintype "passive"))
    )
    (net (code "81") (name "unconnected-(Q1D-IO_L20N_T3_13-PadV19)") (class "Default")
      (node (ref "Q1") (pin "V19") (pinfunction "IO_L20N_T3_13_V19") (pintype "passive"))
    )
    (net (code "82") (name "unconnected-(Q1D-IO_L20P_T3_13-PadU19)") (class "Default")
      (node (ref "Q1") (pin "U19") (pinfunction "IO_L20P_T3_13_U19") (pintype "passive"))
    )
    (net (code "83") (name "unconnected-(Q1D-IO_L21N_T3_DQS_13-PadW18)") (class "Default")
      (node (ref "Q1") (pin "W18") (pinfunction "IO_L21N_T3_DQS_13_W18") (pintype "passive"))
    )
    (net (code "84") (name "unconnected-(Q1D-IO_L21P_T3_DQS_13-PadV18)") (class "Default")
      (node (ref "Q1") (pin "V18") (pinfunction "IO_L21P_T3_DQS_13_V18") (pintype "passive"))
    )
    (net (code "85") (name "unconnected-(Q1D-IO_L22N_T3_13-PadU18)") (class "Default")
      (node (ref "Q1") (pin "U18") (pinfunction "IO_L22N_T3_13_U18") (pintype "passive"))
    )
    (net (code "86") (name "unconnected-(Q1D-IO_L22P_T3_13-PadU17)") (class "Default")
      (node (ref "Q1") (pin "U17") (pinfunction "IO_L22P_T3_13_U17") (pintype "passive"))
    )
    (net (code "87") (name "unconnected-(Q1D-IO_L23N_T3_13-PadW16)") (class "Default")
      (node (ref "Q1") (pin "W16") (pinfunction "IO_L23N_T3_13_W16") (pintype "passive"))
    )
    (net (code "88") (name "unconnected-(Q1D-IO_L23P_T3_13-PadV16)") (class "Default")
      (node (ref "Q1") (pin "V16") (pinfunction "IO_L23P_T3_13_V16") (pintype "passive"))
    )
    (net (code "89") (name "unconnected-(Q1D-IO_L24N_T3_13-PadY17)") (class "Default")
      (node (ref "Q1") (pin "Y17") (pinfunction "IO_L24N_T3_13_Y17") (pintype "passive"))
    )
    (net (code "90") (name "unconnected-(Q1D-IO_L24P_T3_13-PadW17)") (class "Default")
      (node (ref "Q1") (pin "W17") (pinfunction "IO_L24P_T3_13_W17") (pintype "passive"))
    )
    (net (code "91") (name "unconnected-(Q1G-MGTPTXN1_112-PadY4)") (class "Default")
      (node (ref "Q1") (pin "Y4") (pinfunction "MGTPTXN1_112_Y4") (pintype "passive"))
    )
    (net (code "92") (name "unconnected-(Q1G-MGTPTXP1_112-PadW4)") (class "Default")
      (node (ref "Q1") (pin "W4") (pinfunction "MGTPTXP1_112_W4") (pintype "passive"))
    )
    (net (code "93") (name "unconnected-(Q21-BYPASS-Pad4)") (class "Default")
      (node (ref "Q21") (pin "4") (pinfunction "BYPASS_4") (pintype "passive"))
    )
    (net (code "94") (name "unconnected-(Q23-EN-Pad1)") (class "Default")
      (node (ref "Q23") (pin "1") (pinfunction "EN_1") (pintype "passive"))
    )
    (net (code "95") (name "unconnected-(Q24-EN-Pad1)") (class "Default")
      (node (ref "Q24") (pin "1") (pinfunction "EN_1") (pintype "passive"))
    )
    (net (code "96") (name "unconnected-(Q24-GND-Pad7)") (class "Default")
      (node (ref "Q24") (pin "7") (pinfunction "GND_7") (pintype "passive"))
    )
    (net (code "97") (name "unconnected-(Q25-BYPASS-Pad4)") (class "Default")
      (node (ref "Q25") (pin "4") (pinfunction "BYPASS_4") (pintype "passive"))
    )
  )
)
